# TinyGController_V1.net
KiCad netlist of a schematic drawn in EAGLE
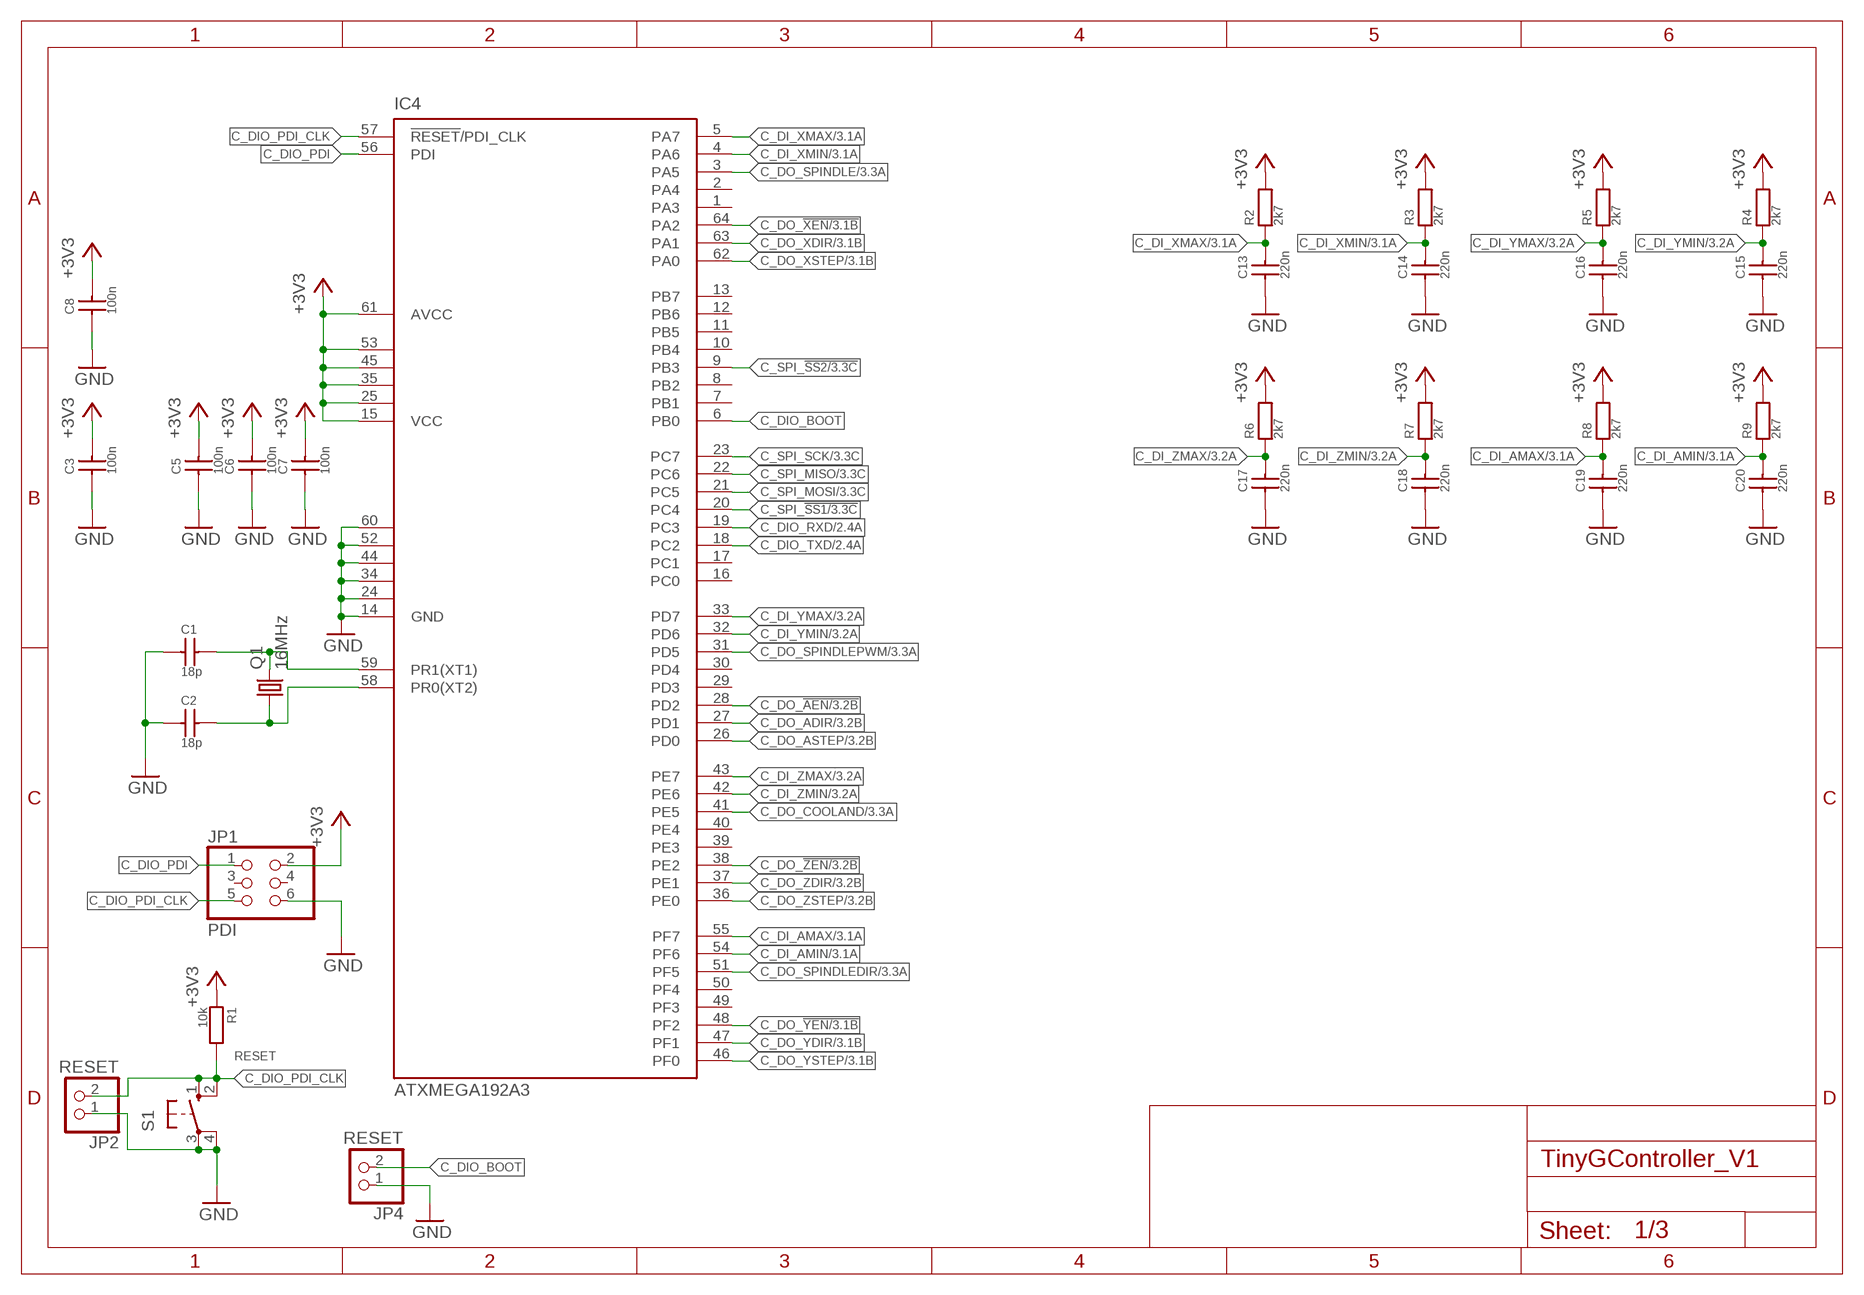
[diagram p0: schematic, sheet 1]
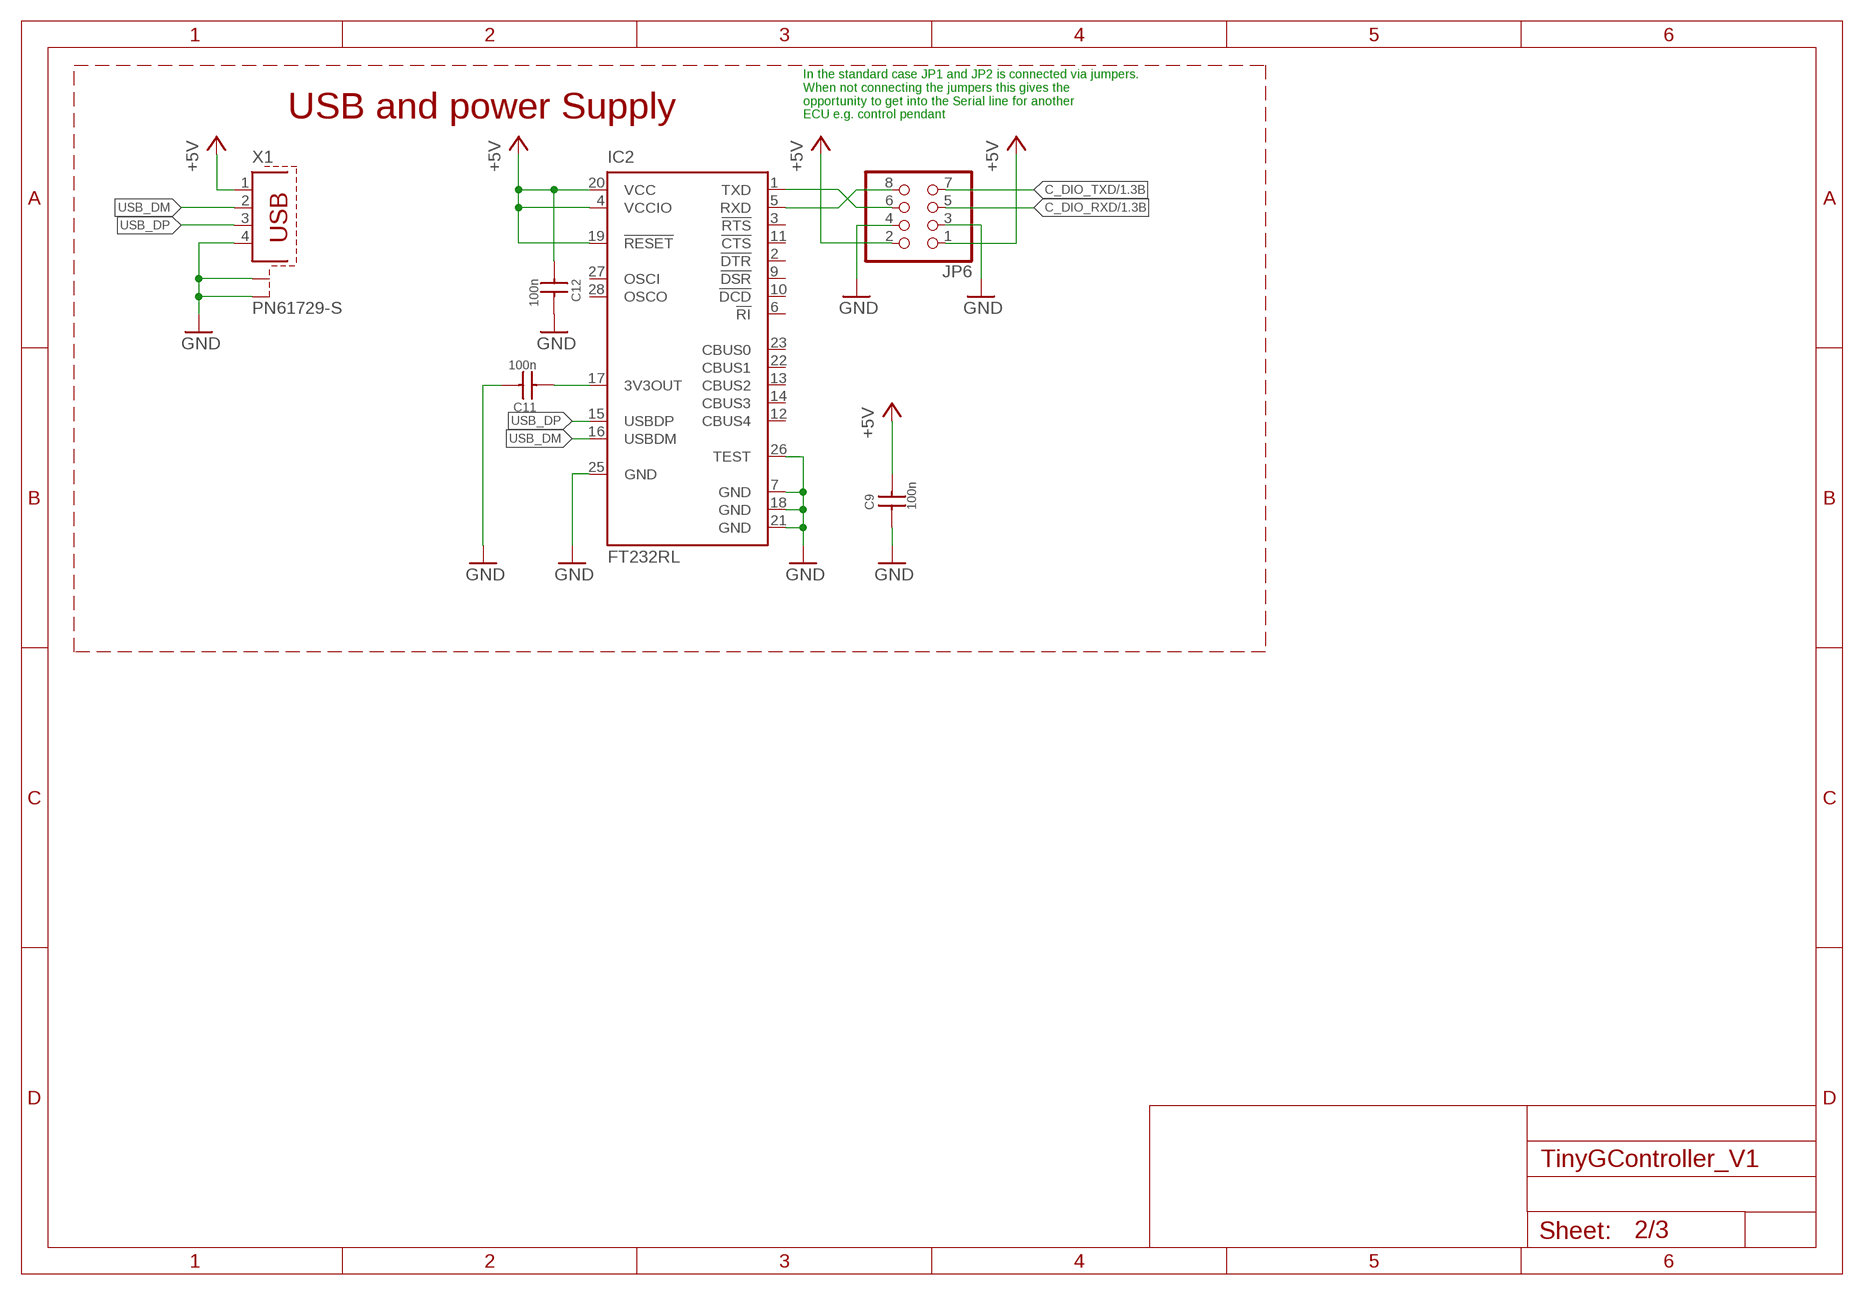
[diagram p1: schematic, sheet 2]
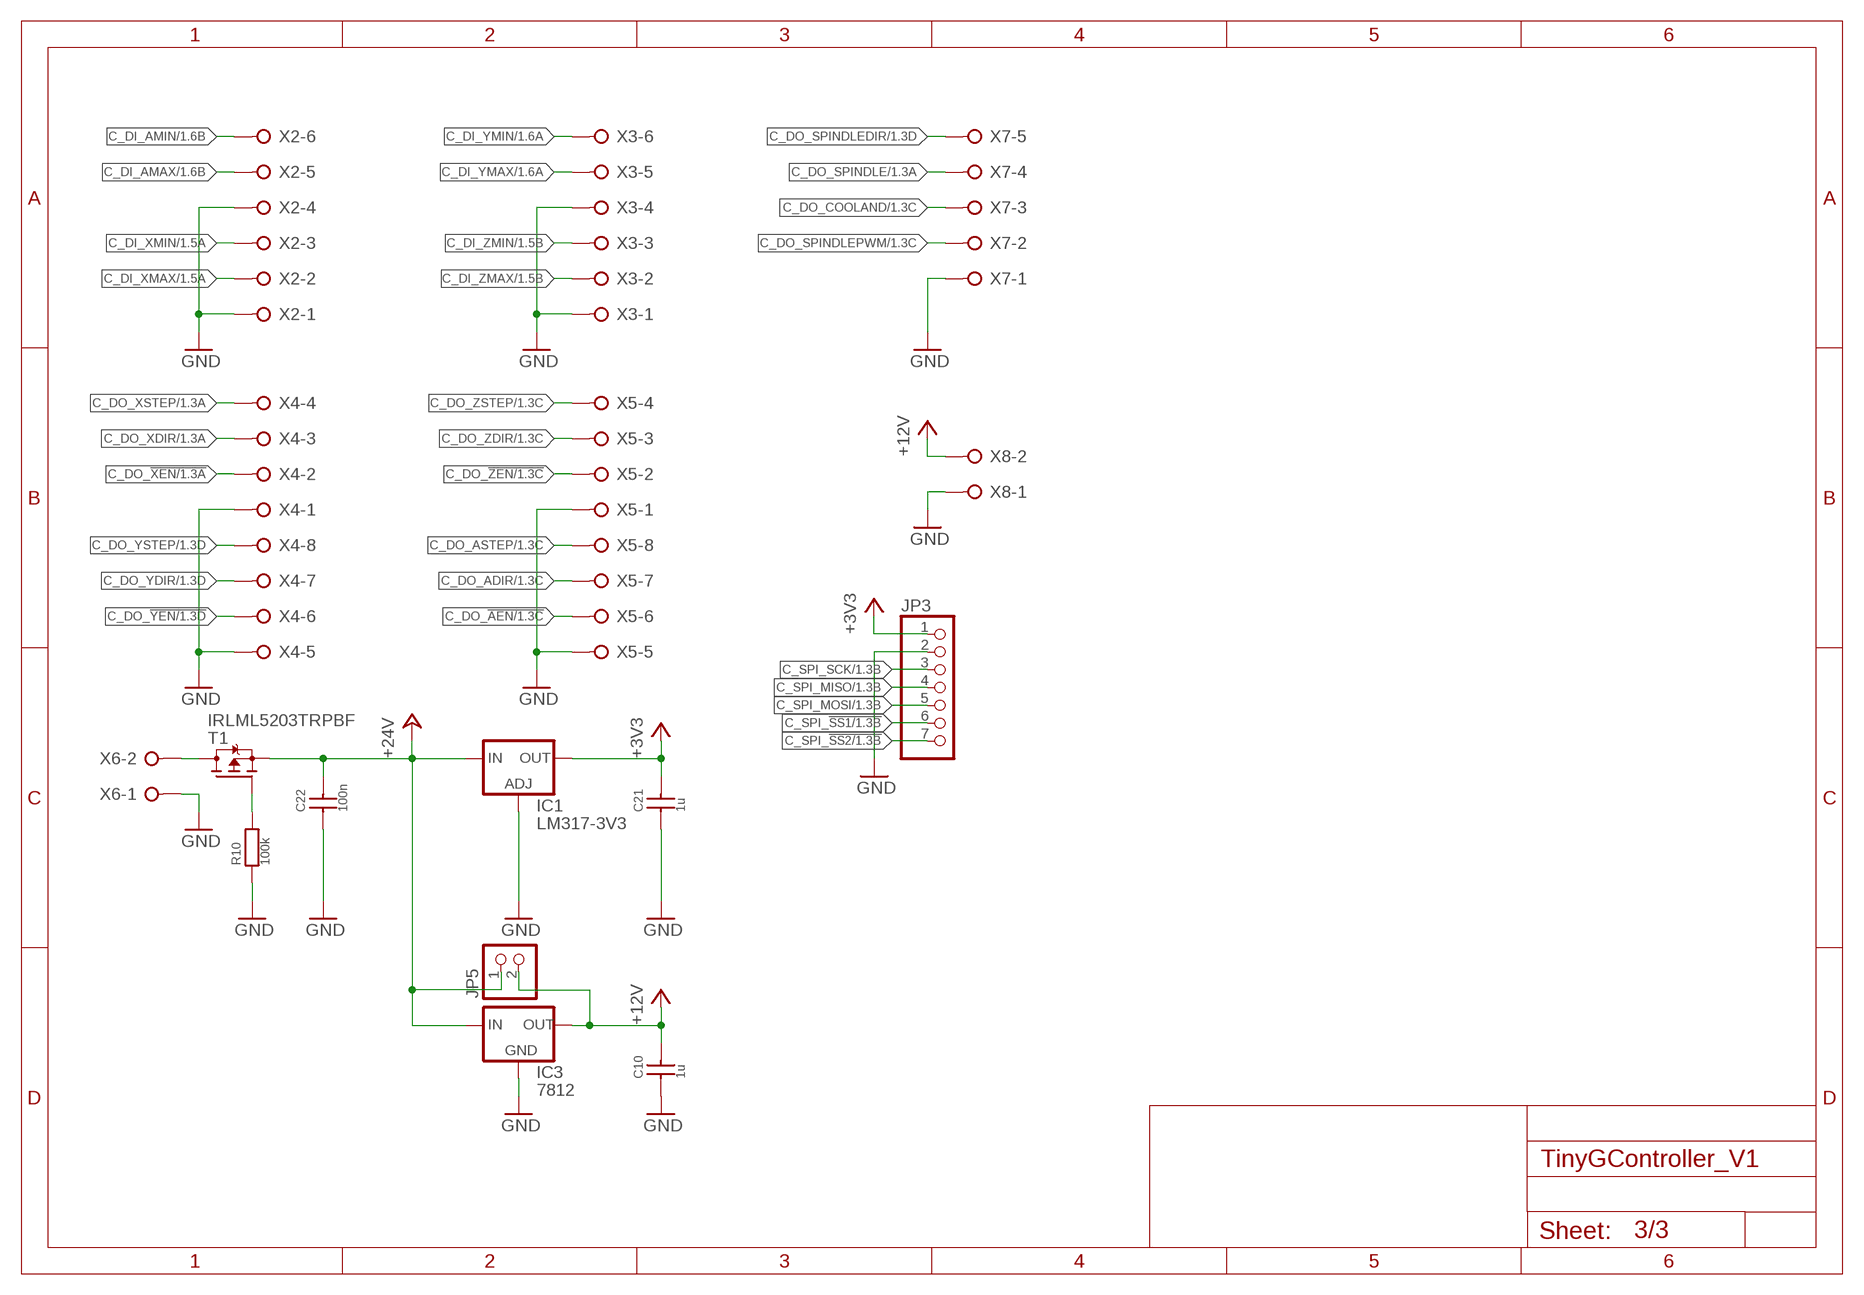
[diagram p2: schematic, sheet 3]

(export (version "E")
  (design (tool "Eeschema 10.0.6"))
  (components
    (comp (ref "C1")
      (value "18p")
      (footprint "eagle-import:C0603")
      (libsource (lib "eagle-import") (part "C_SMD0603"))
    )
    (comp (ref "C2")
      (value "18p")
      (footprint "eagle-import:C0603")
      (libsource (lib "eagle-import") (part "C_SMD0603"))
    )
    (comp (ref "C3")
      (value "100n")
      (footprint "eagle-import:C0603")
      (libsource (lib "eagle-import") (part "C_SMD0603"))
    )
    (comp (ref "C5")
      (value "100n")
      (footprint "eagle-import:C0603")
      (libsource (lib "eagle-import") (part "C_SMD0603"))
    )
    (comp (ref "C6")
      (value "100n")
      (footprint "eagle-import:C0603")
      (libsource (lib "eagle-import") (part "C_SMD0603"))
    )
    (comp (ref "C7")
      (value "100n")
      (footprint "eagle-import:C0603")
      (libsource (lib "eagle-import") (part "C_SMD0603"))
    )
    (comp (ref "C8")
      (value "100n")
      (footprint "eagle-import:C0603")
      (libsource (lib "eagle-import") (part "C_SMD0603"))
    )
    (comp (ref "C13")
      (value "220n")
      (footprint "eagle-import:C0805")
      (libsource (lib "eagle-import") (part "C_SMD0805"))
    )
    (comp (ref "C14")
      (value "220n")
      (footprint "eagle-import:C0805")
      (libsource (lib "eagle-import") (part "C_SMD0805"))
    )
    (comp (ref "C15")
      (value "220n")
      (footprint "eagle-import:C0805")
      (libsource (lib "eagle-import") (part "C_SMD0805"))
    )
    (comp (ref "C16")
      (value "220n")
      (footprint "eagle-import:C0805")
      (libsource (lib "eagle-import") (part "C_SMD0805"))
    )
    (comp (ref "C17")
      (value "220n")
      (footprint "eagle-import:C0805")
      (libsource (lib "eagle-import") (part "C_SMD0805"))
    )
    (comp (ref "C18")
      (value "220n")
      (footprint "eagle-import:C0805")
      (libsource (lib "eagle-import") (part "C_SMD0805"))
    )
    (comp (ref "C19")
      (value "220n")
      (footprint "eagle-import:C0805")
      (libsource (lib "eagle-import") (part "C_SMD0805"))
    )
    (comp (ref "C20")
      (value "220n")
      (footprint "eagle-import:C0805")
      (libsource (lib "eagle-import") (part "C_SMD0805"))
    )
    (comp (ref "IC4")
      (value "ATXMEGA192A3")
      (footprint "eagle-import:TQFP64-0.8MM")
      (libsource (lib "eagle-import") (part "ATXMEGA192A3"))
    )
    (comp (ref "JP1")
      (value "PDI")
      (footprint "eagle-import:2X03")
      (libsource (lib "eagle-import") (part "PINHD-2X3"))
    )
    (comp (ref "JP2")
      (value "RESET")
      (footprint "eagle-import:1X02")
      (libsource (lib "eagle-import") (part "PINHD-1X2"))
    )
    (comp (ref "JP4")
      (value "RESET")
      (footprint "eagle-import:1X02")
      (libsource (lib "eagle-import") (part "PINHD-1X2"))
    )
    (comp (ref "Q1")
      (value "16MHz")
      (footprint "eagle-import:HC49_USSM")
      (libsource (lib "eagle-import") (part "ATS073ASM-1"))
    )
    (comp (ref "R1")
      (value "10k")
      (footprint "eagle-import:R0603")
      (libsource (lib "eagle-import") (part "R0603"))
    )
    (comp (ref "R2")
      (value "2k7")
      (footprint "eagle-import:R0603")
      (libsource (lib "eagle-import") (part "R0603"))
    )
    (comp (ref "R3")
      (value "2k7")
      (footprint "eagle-import:R0603")
      (libsource (lib "eagle-import") (part "R0603"))
    )
    (comp (ref "R4")
      (value "2k7")
      (footprint "eagle-import:R0603")
      (libsource (lib "eagle-import") (part "R0603"))
    )
    (comp (ref "R5")
      (value "2k7")
      (footprint "eagle-import:R0603")
      (libsource (lib "eagle-import") (part "R0603"))
    )
    (comp (ref "R6")
      (value "2k7")
      (footprint "eagle-import:R0603")
      (libsource (lib "eagle-import") (part "R0603"))
    )
    (comp (ref "R7")
      (value "2k7")
      (footprint "eagle-import:R0603")
      (libsource (lib "eagle-import") (part "R0603"))
    )
    (comp (ref "R8")
      (value "2k7")
      (footprint "eagle-import:R0603")
      (libsource (lib "eagle-import") (part "R0603"))
    )
    (comp (ref "R9")
      (value "2k7")
      (footprint "eagle-import:R0603")
      (libsource (lib "eagle-import") (part "R0603"))
    )
    (comp (ref "S1")
      (value "10-XX")
      (footprint "eagle-import:B3F-10XX")
      (fields (field (name "MPN") "B3F-1000"))
      (libsource (lib "eagle-import") (part "10-XX"))
    )
    (comp (ref "C10")
      (value "1u")
      (footprint "eagle-import:C0805")
      (libsource (lib "eagle-import") (part "C_SMD0805"))
    )
    (comp (ref "C21")
      (value "1u")
      (footprint "eagle-import:C0805")
      (libsource (lib "eagle-import") (part "C_SMD0805"))
    )
    (comp (ref "C22")
      (value "100n")
      (footprint "eagle-import:C0805")
      (libsource (lib "eagle-import") (part "C_SMD0805"))
    )
    (comp (ref "IC1")
      (value "LM317-3V3")
      (footprint "eagle-import:SOT223")
      (libsource (lib "eagle-import") (part "LM317?MBSTT3"))
    )
    (comp (ref "IC3")
      (value "7812")
      (footprint "eagle-import:78XXS")
      (libsource (lib "eagle-import") (part "78XXS"))
    )
    (comp (ref "JP3")
      (value "PINHD-1X7")
      (footprint "eagle-import:1X07")
      (libsource (lib "eagle-import") (part "PINHD-1X7"))
    )
    (comp (ref "JP5")
      (value "PINHD-1X2")
      (footprint "eagle-import:1X02")
      (libsource (lib "eagle-import") (part "PINHD-1X2"))
    )
    (comp (ref "R10")
      (value "100k")
      (footprint "eagle-import:R0603")
      (libsource (lib "eagle-import") (part "R0603"))
    )
    (comp (ref "T1")
      (value "IRLML5203TRPBF")
      (footprint "eagle-import:SOT23")
      (libsource (lib "eagle-import") (part "IRLML5203TRPBF"))
    )
    (comp (ref "X2")
      (value "W237-06P")
      (footprint "eagle-import:W237-6P")
      (libsource (lib "eagle-import") (part "W237-06P"))
    )
    (comp (ref "X3")
      (value "W237-06P")
      (footprint "eagle-import:W237-6P")
      (libsource (lib "eagle-import") (part "W237-06P"))
    )
    (comp (ref "X4")
      (value "W237-08P")
      (footprint "eagle-import:W237-8P")
      (libsource (lib "eagle-import") (part "W237-08P"))
    )
    (comp (ref "X5")
      (value "W237-08P")
      (footprint "eagle-import:W237-8P")
      (libsource (lib "eagle-import") (part "W237-08P"))
    )
    (comp (ref "X6")
      (value "W237-02P")
      (footprint "eagle-import:W237-132")
      (libsource (lib "eagle-import") (part "W237-02P"))
    )
    (comp (ref "X7")
      (value "W237-05P")
      (footprint "eagle-import:W237-5P")
      (libsource (lib "eagle-import") (part "W237-05P"))
    )
    (comp (ref "X8")
      (value "W237-02P")
      (footprint "eagle-import:W237-132")
      (libsource (lib "eagle-import") (part "W237-02P"))
    )
    (comp (ref "C9")
      (value "100n")
      (footprint "eagle-import:C0603")
      (libsource (lib "eagle-import") (part "C_SMD0603"))
    )
    (comp (ref "C11")
      (value "100n")
      (footprint "eagle-import:C0603")
      (libsource (lib "eagle-import") (part "C_SMD0603"))
    )
    (comp (ref "C12")
      (value "100n")
      (footprint "eagle-import:C0603")
      (libsource (lib "eagle-import") (part "C_SMD0603"))
    )
    (comp (ref "IC2")
      (value "FT232RL")
      (footprint "eagle-import:SSOP28")
      (libsource (lib "eagle-import") (part "FT232RL"))
    )
    (comp (ref "JP6")
      (value "PINHD-2X4")
      (footprint "eagle-import:2X04")
      (libsource (lib "eagle-import") (part "PINHD-2X4"))
    )
    (comp (ref "X1")
      (value "PN61729-S")
      (footprint "eagle-import:PN61729-S")
      (libsource (lib "eagle-import") (part "PN61729-S"))
    )
  )
  (nets
    (net (code "1") (name "+3V3") (class "Default")
      (node (ref "C21") (pin "2") (pinfunction "P$2_2") (pintype "passive"))
      (node (ref "C3") (pin "2") (pinfunction "P$2_2") (pintype "passive"))
      (node (ref "C5") (pin "2") (pinfunction "P$2_2") (pintype "passive"))
      (node (ref "C6") (pin "2") (pinfunction "P$2_2") (pintype "passive"))
      (node (ref "C7") (pin "2") (pinfunction "P$2_2") (pintype "passive"))
      (node (ref "C8") (pin "2") (pinfunction "P$2_2") (pintype "passive"))
      (node (ref "IC1") (pin "4") (pinfunction "OUT_4") (pintype "passive"))
      (node (ref "IC4") (pin "15") (pinfunction "VCC_15") (pintype "power_in"))
      (node (ref "IC4") (pin "25") (pinfunction "VCC1_25") (pintype "power_in"))
      (node (ref "IC4") (pin "35") (pinfunction "VCC2_35") (pintype "power_in"))
      (node (ref "IC4") (pin "45") (pinfunction "VCC3_45") (pintype "power_in"))
      (node (ref "IC4") (pin "53") (pinfunction "VCC4_53") (pintype "power_in"))
      (node (ref "IC4") (pin "61") (pinfunction "AVCC_61") (pintype "power_in"))
      (node (ref "JP1") (pin "2") (pinfunction "2_2") (pintype "passive"))
      (node (ref "JP3") (pin "1") (pinfunction "1_1") (pintype "passive"))
      (node (ref "R1") (pin "1") (pinfunction "P$1_1") (pintype "passive"))
      (node (ref "R2") (pin "2") (pinfunction "P$2_2") (pintype "passive"))
      (node (ref "R3") (pin "2") (pinfunction "P$2_2") (pintype "passive"))
      (node (ref "R4") (pin "2") (pinfunction "P$2_2") (pintype "passive"))
      (node (ref "R5") (pin "2") (pinfunction "P$2_2") (pintype "passive"))
      (node (ref "R6") (pin "2") (pinfunction "P$2_2") (pintype "passive"))
      (node (ref "R7") (pin "2") (pinfunction "P$2_2") (pintype "passive"))
      (node (ref "R8") (pin "2") (pinfunction "P$2_2") (pintype "passive"))
      (node (ref "R9") (pin "2") (pinfunction "P$2_2") (pintype "passive"))
    )
    (net (code "2") (name "+5V") (class "Default")
      (node (ref "C12") (pin "1") (pinfunction "P$1_1") (pintype "passive"))
      (node (ref "C9") (pin "2") (pinfunction "P$2_2") (pintype "passive"))
      (node (ref "IC2") (pin "19") (pinfunction "~{RESET}_19") (pintype "input"))
      (node (ref "IC2") (pin "20") (pinfunction "VCC_20") (pintype "power_in"))
      (node (ref "IC2") (pin "4") (pinfunction "VCCIO_4") (pintype "power_in"))
      (node (ref "JP6") (pin "1") (pinfunction "1_1") (pintype "passive"))
      (node (ref "JP6") (pin "2") (pinfunction "2_2") (pintype "passive"))
      (node (ref "X1") (pin "1") (pinfunction "1_1") (pintype "passive"))
    )
    (net (code "3") (name "+12V") (class "Default")
      (node (ref "C10") (pin "2") (pinfunction "P$2_2") (pintype "passive"))
      (node (ref "IC3") (pin "OUT") (pinfunction "OUT_OUT") (pintype "passive"))
      (node (ref "JP5") (pin "2") (pinfunction "2_2") (pintype "passive"))
      (node (ref "X8") (pin "2") (pinfunction "KL_2") (pintype "passive"))
    )
    (net (code "4") (name "+24V") (class "Default")
      (node (ref "C22") (pin "2") (pinfunction "P$2_2") (pintype "passive"))
      (node (ref "IC1") (pin "3") (pinfunction "IN_3") (pintype "input"))
      (node (ref "IC3") (pin "IN") (pinfunction "IN_IN") (pintype "input"))
      (node (ref "JP5") (pin "1") (pinfunction "1_1") (pintype "passive"))
      (node (ref "T1") (pin "2") (pinfunction "S_2") (pintype "passive"))
    )
    (net (code "5") (name "C_DIO_BOOT") (class "Default")
      (node (ref "IC4") (pin "6") (pinfunction "PB0_6") (pintype "bidirectional"))
      (node (ref "JP4") (pin "2") (pinfunction "2_2") (pintype "passive"))
    )
    (net (code "6") (name "C_DIO_PDI") (class "Default")
      (node (ref "IC4") (pin "56") (pinfunction "PDI_56") (pintype "input"))
      (node (ref "JP1") (pin "1") (pinfunction "1_1") (pintype "passive"))
    )
    (net (code "7") (name "C_DIO_PDI_CLK") (class "Default")
      (node (ref "IC4") (pin "57") (pinfunction "~{RESET}/PDI_CLK_57") (pintype "input"))
      (node (ref "JP1") (pin "5") (pinfunction "5_5") (pintype "passive"))
      (node (ref "JP2") (pin "2") (pinfunction "2_2") (pintype "passive"))
      (node (ref "R1") (pin "2") (pinfunction "P$2_2") (pintype "passive"))
      (node (ref "S1") (pin "1") (pinfunction "S_1") (pintype "passive"))
      (node (ref "S1") (pin "2") (pinfunction "S1_2") (pintype "passive"))
    )
    (net (code "8") (name "C_DIO_RXD") (class "Default")
      (node (ref "IC4") (pin "19") (pinfunction "PC3_19") (pintype "bidirectional"))
      (node (ref "JP6") (pin "5") (pinfunction "5_5") (pintype "passive"))
    )
    (net (code "9") (name "C_DIO_TXD") (class "Default")
      (node (ref "IC4") (pin "18") (pinfunction "PC2_18") (pintype "bidirectional"))
      (node (ref "JP6") (pin "7") (pinfunction "7_7") (pintype "passive"))
    )
    (net (code "10") (name "C_DI_AMAX") (class "Default")
      (node (ref "C19") (pin "2") (pinfunction "P$2_2") (pintype "passive"))
      (node (ref "IC4") (pin "55") (pinfunction "PF7_55") (pintype "bidirectional"))
      (node (ref "R8") (pin "1") (pinfunction "P$1_1") (pintype "passive"))
      (node (ref "X2") (pin "5") (pinfunction "KL_5") (pintype "passive"))
    )
    (net (code "11") (name "C_DI_AMIN") (class "Default")
      (node (ref "C20") (pin "2") (pinfunction "P$2_2") (pintype "passive"))
      (node (ref "IC4") (pin "54") (pinfunction "PF6_54") (pintype "bidirectional"))
      (node (ref "R9") (pin "1") (pinfunction "P$1_1") (pintype "passive"))
      (node (ref "X2") (pin "6") (pinfunction "KL_6") (pintype "passive"))
    )
    (net (code "12") (name "C_DI_XMAX") (class "Default")
      (node (ref "C13") (pin "2") (pinfunction "P$2_2") (pintype "passive"))
      (node (ref "IC4") (pin "5") (pinfunction "PA7_5") (pintype "bidirectional"))
      (node (ref "R2") (pin "1") (pinfunction "P$1_1") (pintype "passive"))
      (node (ref "X2") (pin "2") (pinfunction "KL_2") (pintype "passive"))
    )
    (net (code "13") (name "C_DI_XMIN") (class "Default")
      (node (ref "C14") (pin "2") (pinfunction "P$2_2") (pintype "passive"))
      (node (ref "IC4") (pin "4") (pinfunction "PA6_4") (pintype "bidirectional"))
      (node (ref "R3") (pin "1") (pinfunction "P$1_1") (pintype "passive"))
      (node (ref "X2") (pin "3") (pinfunction "KL_3") (pintype "passive"))
    )
    (net (code "14") (name "C_DI_YMAX") (class "Default")
      (node (ref "C16") (pin "2") (pinfunction "P$2_2") (pintype "passive"))
      (node (ref "IC4") (pin "33") (pinfunction "PD7_33") (pintype "bidirectional"))
      (node (ref "R5") (pin "1") (pinfunction "P$1_1") (pintype "passive"))
      (node (ref "X3") (pin "5") (pinfunction "KL_5") (pintype "passive"))
    )
    (net (code "15") (name "C_DI_YMIN") (class "Default")
      (node (ref "C15") (pin "2") (pinfunction "P$2_2") (pintype "passive"))
      (node (ref "IC4") (pin "32") (pinfunction "PD6_32") (pintype "bidirectional"))
      (node (ref "R4") (pin "1") (pinfunction "P$1_1") (pintype "passive"))
      (node (ref "X3") (pin "6") (pinfunction "KL_6") (pintype "passive"))
    )
    (net (code "16") (name "C_DI_ZMAX") (class "Default")
      (node (ref "C17") (pin "2") (pinfunction "P$2_2") (pintype "passive"))
      (node (ref "IC4") (pin "43") (pinfunction "PE7_43") (pintype "bidirectional"))
      (node (ref "R6") (pin "1") (pinfunction "P$1_1") (pintype "passive"))
      (node (ref "X3") (pin "2") (pinfunction "KL_2") (pintype "passive"))
    )
    (net (code "17") (name "C_DI_ZMIN") (class "Default")
      (node (ref "C18") (pin "2") (pinfunction "P$2_2") (pintype "passive"))
      (node (ref "IC4") (pin "42") (pinfunction "PE6_42") (pintype "bidirectional"))
      (node (ref "R7") (pin "1") (pinfunction "P$1_1") (pintype "passive"))
      (node (ref "X3") (pin "3") (pinfunction "KL_3") (pintype "passive"))
    )
    (net (code "18") (name "C_DO_ADIR") (class "Default")
      (node (ref "IC4") (pin "27") (pinfunction "PD1_27") (pintype "bidirectional"))
      (node (ref "X5") (pin "7") (pinfunction "KL_7") (pintype "passive"))
    )
    (net (code "19") (name "C_DO_ASTEP") (class "Default")
      (node (ref "IC4") (pin "26") (pinfunction "PD0_26") (pintype "bidirectional"))
      (node (ref "X5") (pin "8") (pinfunction "KL_8") (pintype "passive"))
    )
    (net (code "20") (name "C_DO_COOLAND") (class "Default")
      (node (ref "IC4") (pin "41") (pinfunction "PE5_41") (pintype "bidirectional"))
      (node (ref "X7") (pin "3") (pinfunction "KL_3") (pintype "passive"))
    )
    (net (code "21") (name "C_DO_SPINDLE") (class "Default")
      (node (ref "IC4") (pin "3") (pinfunction "PA5_3") (pintype "bidirectional"))
      (node (ref "X7") (pin "4") (pinfunction "KL_4") (pintype "passive"))
    )
    (net (code "22") (name "C_DO_SPINDLEDIR") (class "Default")
      (node (ref "IC4") (pin "51") (pinfunction "PF5_51") (pintype "bidirectional"))
      (node (ref "X7") (pin "5") (pinfunction "KL_5") (pintype "passive"))
    )
    (net (code "23") (name "C_DO_SPINDLEPWM") (class "Default")
      (node (ref "IC4") (pin "31") (pinfunction "PD5_31") (pintype "bidirectional"))
      (node (ref "X7") (pin "2") (pinfunction "KL_2") (pintype "passive"))
    )
    (net (code "24") (name "C_DO_XDIR") (class "Default")
      (node (ref "IC4") (pin "63") (pinfunction "PA1_63") (pintype "bidirectional"))
      (node (ref "X4") (pin "3") (pinfunction "KL_3") (pintype "passive"))
    )
    (net (code "25") (name "C_DO_XSTEP") (class "Default")
      (node (ref "IC4") (pin "62") (pinfunction "PA0_62") (pintype "bidirectional"))
      (node (ref "X4") (pin "4") (pinfunction "KL_4") (pintype "passive"))
    )
    (net (code "26") (name "C_DO_YDIR") (class "Default")
      (node (ref "IC4") (pin "47") (pinfunction "PF1_47") (pintype "bidirectional"))
      (node (ref "X4") (pin "7") (pinfunction "KL_7") (pintype "passive"))
    )
    (net (code "27") (name "C_DO_YSTEP") (class "Default")
      (node (ref "IC4") (pin "46") (pinfunction "PF0_46") (pintype "bidirectional"))
      (node (ref "X4") (pin "8") (pinfunction "KL_8") (pintype "passive"))
    )
    (net (code "28") (name "C_DO_ZDIR") (class "Default")
      (node (ref "IC4") (pin "37") (pinfunction "PE1_37") (pintype "bidirectional"))
      (node (ref "X5") (pin "3") (pinfunction "KL_3") (pintype "passive"))
    )
    (net (code "29") (name "C_DO_ZSTEP") (class "Default")
      (node (ref "IC4") (pin "36") (pinfunction "PE0_36") (pintype "bidirectional"))
      (node (ref "X5") (pin "4") (pinfunction "KL_4") (pintype "passive"))
    )
    (net (code "30") (name "C_DO_~{AEN}") (class "Default")
      (node (ref "IC4") (pin "28") (pinfunction "PD2_28") (pintype "bidirectional"))
      (node (ref "X5") (pin "6") (pinfunction "KL_6") (pintype "passive"))
    )
    (net (code "31") (name "C_DO_~{XEN}") (class "Default")
      (node (ref "IC4") (pin "64") (pinfunction "PA2_64") (pintype "bidirectional"))
      (node (ref "X4") (pin "2") (pinfunction "KL_2") (pintype "passive"))
    )
    (net (code "32") (name "C_DO_~{YEN}") (class "Default")
      (node (ref "IC4") (pin "48") (pinfunction "PF2_48") (pintype "bidirectional"))
      (node (ref "X4") (pin "6") (pinfunction "KL_6") (pintype "passive"))
    )
    (net (code "33") (name "C_DO_~{ZEN}") (class "Default")
      (node (ref "IC4") (pin "38") (pinfunction "PE2_38") (pintype "bidirectional"))
      (node (ref "X5") (pin "2") (pinfunction "KL_2") (pintype "passive"))
    )
    (net (code "34") (name "C_SPI_MISO") (class "Default")
      (node (ref "IC4") (pin "22") (pinfunction "PC6_22") (pintype "bidirectional"))
      (node (ref "JP3") (pin "4") (pinfunction "4_4") (pintype "passive"))
    )
    (net (code "35") (name "C_SPI_MOSI") (class "Default")
      (node (ref "IC4") (pin "21") (pinfunction "PC5_21") (pintype "bidirectional"))
      (node (ref "JP3") (pin "5") (pinfunction "5_5") (pintype "passive"))
    )
    (net (code "36") (name "C_SPI_SCK") (class "Default")
      (node (ref "IC4") (pin "23") (pinfunction "PC7_23") (pintype "bidirectional"))
      (node (ref "JP3") (pin "3") (pinfunction "3_3") (pintype "passive"))
    )
    (net (code "37") (name "C_SPI_~{SS1}") (class "Default")
      (node (ref "IC4") (pin "20") (pinfunction "PC4_20") (pintype "bidirectional"))
      (node (ref "JP3") (pin "6") (pinfunction "6_6") (pintype "passive"))
    )
    (net (code "38") (name "C_SPI_~{SS2}") (class "Default")
      (node (ref "IC4") (pin "9") (pinfunction "PB3_9") (pintype "bidirectional"))
      (node (ref "JP3") (pin "7") (pinfunction "7_7") (pintype "passive"))
    )
    (net (code "39") (name "GND") (class "Default")
      (node (ref "C1") (pin "1") (pinfunction "P$1_1") (pintype "passive"))
      (node (ref "C10") (pin "1") (pinfunction "P$1_1") (pintype "passive"))
      (node (ref "C11") (pin "2") (pinfunction "P$2_2") (pintype "passive"))
      (node (ref "C12") (pin "2") (pinfunction "P$2_2") (pintype "passive"))
      (node (ref "C13") (pin "1") (pinfunction "P$1_1") (pintype "passive"))
      (node (ref "C14") (pin "1") (pinfunction "P$1_1") (pintype "passive"))
      (node (ref "C15") (pin "1") (pinfunction "P$1_1") (pintype "passive"))
      (node (ref "C16") (pin "1") (pinfunction "P$1_1") (pintype "passive"))
      (node (ref "C17") (pin "1") (pinfunction "P$1_1") (pintype "passive"))
      (node (ref "C18") (pin "1") (pinfunction "P$1_1") (pintype "passive"))
      (node (ref "C19") (pin "1") (pinfunction "P$1_1") (pintype "passive"))
      (node (ref "C2") (pin "1") (pinfunction "P$1_1") (pintype "passive"))
      (node (ref "C20") (pin "1") (pinfunction "P$1_1") (pintype "passive"))
      (node (ref "C21") (pin "1") (pinfunction "P$1_1") (pintype "passive"))
      (node (ref "C22") (pin "1") (pinfunction "P$1_1") (pintype "passive"))
      (node (ref "C3") (pin "1") (pinfunction "P$1_1") (pintype "passive"))
      (node (ref "C5") (pin "1") (pinfunction "P$1_1") (pintype "passive"))
      (node (ref "C6") (pin "1") (pinfunction "P$1_1") (pintype "passive"))
      (node (ref "C7") (pin "1") (pinfunction "P$1_1") (pintype "passive"))
      (node (ref "C8") (pin "1") (pinfunction "P$1_1") (pintype "passive"))
      (node (ref "C9") (pin "1") (pinfunction "P$1_1") (pintype "passive"))
      (node (ref "IC1") (pin "1") (pinfunction "ADJ_1") (pintype "input"))
      (node (ref "IC2") (pin "18") (pinfunction "GND_18") (pintype "power_in"))
      (node (ref "IC2") (pin "21") (pinfunction "GND_21") (pintype "power_in"))
      (node (ref "IC2") (pin "25") (pinfunction "GND_25") (pintype "power_in"))
      (node (ref "IC2") (pin "26") (pinfunction "TEST_26") (pintype "input"))
      (node (ref "IC2") (pin "7") (pinfunction "GND_7") (pintype "power_in"))
      (node (ref "IC3") (pin "GND") (pinfunction "GND_GND") (pintype "input"))
      (node (ref "IC4") (pin "14") (pinfunction "GND_14") (pintype "power_in"))
      (node (ref "IC4") (pin "24") (pinfunction "GND1_24") (pintype "power_in"))
      (node (ref "IC4") (pin "34") (pinfunction "GND2_34") (pintype "power_in"))
      (node (ref "IC4") (pin "44") (pinfunction "GND3_44") (pintype "power_in"))
      (node (ref "IC4") (pin "52") (pinfunction "GND4_52") (pintype "power_in"))
      (node (ref "IC4") (pin "60") (pinfunction "GND5_60") (pintype "power_in"))
      (node (ref "JP1") (pin "6") (pinfunction "6_6") (pintype "passive"))
      (node (ref "JP2") (pin "1") (pinfunction "1_1") (pintype "passive"))
      (node (ref "JP3") (pin "2") (pinfunction "2_2") (pintype "passive"))
      (node (ref "JP4") (pin "1") (pinfunction "1_1") (pintype "passive"))
      (node (ref "JP6") (pin "3") (pinfunction "3_3") (pintype "passive"))
      (node (ref "JP6") (pin "4") (pinfunction "4_4") (pintype "passive"))
      (node (ref "R10") (pin "1") (pinfunction "P$1_1") (pintype "passive"))
      (node (ref "S1") (pin "3") (pinfunction "P_3") (pintype "passive"))
      (node (ref "S1") (pin "4") (pinfunction "P1_4") (pintype "passive"))
      (node (ref "X1") (pin "4") (pinfunction "4_4") (pintype "passive"))
      (node (ref "X1") (pin "S1") (pinfunction "S1_S1") (pintype "passive"))
      (node (ref "X1") (pin "S2") (pinfunction "S2_S2") (pintype "passive"))
      (node (ref "X2") (pin "1") (pinfunction "KL_1") (pintype "passive"))
      (node (ref "X2") (pin "4") (pinfunction "KL_4") (pintype "passive"))
      (node (ref "X3") (pin "1") (pinfunction "KL_1") (pintype "passive"))
      (node (ref "X3") (pin "4") (pinfunction "KL_4") (pintype "passive"))
      (node (ref "X4") (pin "1") (pinfunction "KL_1") (pintype "passive"))
      (node (ref "X4") (pin "5") (pinfunction "KL_5") (pintype "passive"))
      (node (ref "X5") (pin "1") (pinfunction "KL_1") (pintype "passive"))
      (node (ref "X5") (pin "5") (pinfunction "KL_5") (pintype "passive"))
      (node (ref "X6") (pin "1") (pinfunction "KL_1") (pintype "passive"))
      (node (ref "X7") (pin "1") (pinfunction "KL_1") (pintype "passive"))
      (node (ref "X8") (pin "1") (pinfunction "KL_1") (pintype "passive"))
    )
    (net (code "40") (name "Net-(C1-P$2)") (class "Default")
      (node (ref "C1") (pin "2") (pinfunction "P$2_2") (pintype "passive"))
      (node (ref "IC4") (pin "59") (pinfunction "PR1(XT1)_59") (pintype "bidirectional"))
      (node (ref "Q1") (pin "2") (pinfunction "2_2") (pintype "passive"))
    )
    (net (code "41") (name "Net-(C2-P$2)") (class "Default")
      (node (ref "C2") (pin "2") (pinfunction "P$2_2") (pintype "passive"))
      (node (ref "IC4") (pin "58") (pinfunction "PR0(XT2)_58") (pintype "bidirectional"))
      (node (ref "Q1") (pin "1") (pinfunction "1_1") (pintype "passive"))
    )
    (net (code "42") (name "Net-(C11-P$1)") (class "Default")
      (node (ref "C11") (pin "1") (pinfunction "P$1_1") (pintype "passive"))
      (node (ref "IC2") (pin "17") (pinfunction "3V3OUT_17") (pintype "output"))
    )
    (net (code "43") (name "Net-(IC2-RXD)") (class "Default")
      (node (ref "IC2") (pin "5") (pinfunction "RXD_5") (pintype "input"))
      (node (ref "JP6") (pin "8") (pinfunction "8_8") (pintype "passive"))
    )
    (net (code "44") (name "Net-(IC2-TXD)") (class "Default")
      (node (ref "IC2") (pin "1") (pinfunction "TXD_1") (pintype "output"))
      (node (ref "JP6") (pin "6") (pinfunction "6_6") (pintype "passive"))
    )
    (net (code "45") (name "Net-(R10-P$2)") (class "Default")
      (node (ref "R10") (pin "2") (pinfunction "P$2_2") (pintype "passive"))
      (node (ref "T1") (pin "1") (pinfunction "G_1") (pintype "passive"))
    )
    (net (code "46") (name "Net-(T1-D)") (class "Default")
      (node (ref "T1") (pin "3") (pinfunction "D_3") (pintype "passive"))
      (node (ref "X6") (pin "2") (pinfunction "KL_2") (pintype "passive"))
    )
    (net (code "47") (name "USB_DM") (class "Default")
      (node (ref "IC2") (pin "16") (pinfunction "USBDM_16") (pintype "bidirectional"))
      (node (ref "X1") (pin "2") (pinfunction "2_2") (pintype "passive"))
    )
    (net (code "48") (name "USB_DP") (class "Default")
      (node (ref "IC2") (pin "15") (pinfunction "USBDP_15") (pintype "bidirectional"))
      (node (ref "X1") (pin "3") (pinfunction "3_3") (pintype "passive"))
    )
    (net (code "49") (name "unconnected-(IC2-CBUS0-Pad23)") (class "Default")
      (node (ref "IC2") (pin "23") (pinfunction "CBUS0_23") (pintype "bidirectional"))
    )
    (net (code "50") (name "unconnected-(IC2-CBUS1-Pad22)") (class "Default")
      (node (ref "IC2") (pin "22") (pinfunction "CBUS1_22") (pintype "bidirectional"))
    )
    (net (code "51") (name "unconnected-(IC2-CBUS2-Pad13)") (class "Default")
      (node (ref "IC2") (pin "13") (pinfunction "CBUS2_13") (pintype "bidirectional"))
    )
    (net (code "52") (name "unconnected-(IC2-CBUS3-Pad14)") (class "Default")
      (node (ref "IC2") (pin "14") (pinfunction "CBUS3_14") (pintype "bidirectional"))
    )
    (net (code "53") (name "unconnected-(IC2-CBUS4-Pad12)") (class "Default")
      (node (ref "IC2") (pin "12") (pinfunction "CBUS4_12") (pintype "bidirectional"))
    )
    (net (code "54") (name "unconnected-(IC2-OSCI-Pad27)") (class "Default")
      (node (ref "IC2") (pin "27") (pinfunction "OSCI_27") (pintype "input"))
    )
    (net (code "55") (name "unconnected-(IC2-OSCO-Pad28)") (class "Default")
      (node (ref "IC2") (pin "28") (pinfunction "OSCO_28") (pintype "output"))
    )
    (net (code "56") (name "unconnected-(IC2-~{CTS}-Pad11)") (class "Default")
      (node (ref "IC2") (pin "11") (pinfunction "~{CTS}_11") (pintype "input"))
    )
    (net (code "57") (name "unconnected-(IC2-~{DCD}-Pad10)") (class "Default")
      (node (ref "IC2") (pin "10") (pinfunction "~{DCD}_10") (pintype "input"))
    )
    (net (code "58") (name "unconnected-(IC2-~{DSR}-Pad9)") (class "Default")
      (node (ref "IC2") (pin "9") (pinfunction "~{DSR}_9") (pintype "input"))
    )
    (net (code "59") (name "unconnected-(IC2-~{DTR}-Pad2)") (class "Default")
      (node (ref "IC2") (pin "2") (pinfunction "~{DTR}_2") (pintype "output"))
    )
    (net (code "60") (name "unconnected-(IC2-~{RI}-Pad6)") (class "Default")
      (node (ref "IC2") (pin "6") (pinfunction "~{RI}_6") (pintype "input"))
    )
    (net (code "61") (name "unconnected-(IC2-~{RTS}-Pad3)") (class "Default")
      (node (ref "IC2") (pin "3") (pinfunction "~{RTS}_3") (pintype "output"))
    )
    (net (code "62") (name "unconnected-(IC4-PA3-Pad1)") (class "Default")
      (node (ref "IC4") (pin "1") (pinfunction "PA3_1") (pintype "bidirectional"))
    )
    (net (code "63") (name "unconnected-(IC4-PA4-Pad2)") (class "Default")
      (node (ref "IC4") (pin "2") (pinfunction "PA4_2") (pintype "bidirectional"))
    )
    (net (code "64") (name "unconnected-(IC4-PB1-Pad7)") (class "Default")
      (node (ref "IC4") (pin "7") (pinfunction "PB1_7") (pintype "bidirectional"))
    )
    (net (code "65") (name "unconnected-(IC4-PB2-Pad8)") (class "Default")
      (node (ref "IC4") (pin "8") (pinfunction "PB2_8") (pintype "bidirectional"))
    )
    (net (code "66") (name "unconnected-(IC4-PB4-Pad10)") (class "Default")
      (node (ref "IC4") (pin "10") (pinfunction "PB4_10") (pintype "bidirectional"))
    )
    (net (code "67") (name "unconnected-(IC4-PB5-Pad11)") (class "Default")
      (node (ref "IC4") (pin "11") (pinfunction "PB5_11") (pintype "bidirectional"))
    )
    (net (code "68") (name "unconnected-(IC4-PB6-Pad12)") (class "Default")
      (node (ref "IC4") (pin "12") (pinfunction "PB6_12") (pintype "bidirectional"))
    )
    (net (code "69") (name "unconnected-(IC4-PB7-Pad13)") (class "Default")
      (node (ref "IC4") (pin "13") (pinfunction "PB7_13") (pintype "bidirectional"))
    )
    (net (code "70") (name "unconnected-(IC4-PC0-Pad16)") (class "Default")
      (node (ref "IC4") (pin "16") (pinfunction "PC0_16") (pintype "bidirectional"))
    )
    (net (code "71") (name "unconnected-(IC4-PC1-Pad17)") (class "Default")
      (node (ref "IC4") (pin "17") (pinfunction "PC1_17") (pintype "bidirectional"))
    )
    (net (code "72") (name "unconnected-(IC4-PD3-Pad29)") (class "Default")
      (node (ref "IC4") (pin "29") (pinfunction "PD3_29") (pintype "bidirectional"))
    )
    (net (code "73") (name "unconnected-(IC4-PD4-Pad30)") (class "Default")
      (node (ref "IC4") (pin "30") (pinfunction "PD4_30") (pintype "bidirectional"))
    )
    (net (code "74") (name "unconnected-(IC4-PE3-Pad39)") (class "Default")
      (node (ref "IC4") (pin "39") (pinfunction "PE3_39") (pintype "bidirectional"))
    )
    (net (code "75") (name "unconnected-(IC4-PE4-Pad40)") (class "Default")
      (node (ref "IC4") (pin "40") (pinfunction "PE4_40") (pintype "bidirectional"))
    )
    (net (code "76") (name "unconnected-(IC4-PF3-Pad49)") (class "Default")
      (node (ref "IC4") (pin "49") (pinfunction "PF3_49") (pintype "bidirectional"))
    )
    (net (code "77") (name "unconnected-(IC4-PF4-Pad50)") (class "Default")
      (node (ref "IC4") (pin "50") (pinfunction "PF4_50") (pintype "bidirectional"))
    )
    (net (code "78") (name "unconnected-(JP1-Pad3)") (class "Default")
      (node (ref "JP1") (pin "3") (pinfunction "3_3") (pintype "passive"))
    )
    (net (code "79") (name "unconnected-(JP1-Pad4)") (class "Default")
      (node (ref "JP1") (pin "4") (pinfunction "4_4") (pintype "passive"))
    )
  )
)
